# ServoCape_Rev2.net
KiCad netlist of a schematic drawn in EAGLE
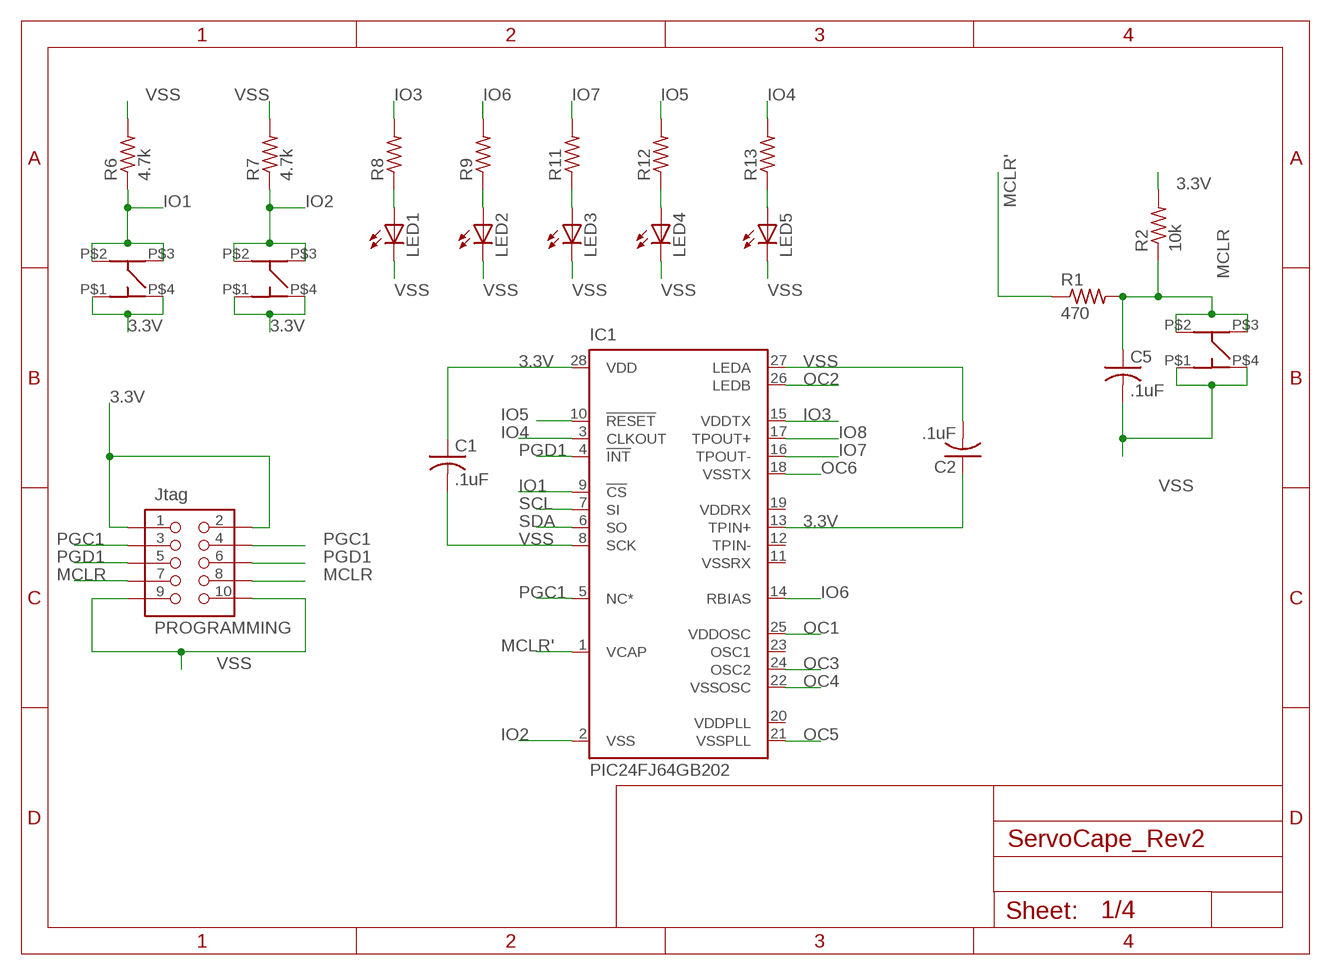
[diagram p0: schematic, sheet 1]
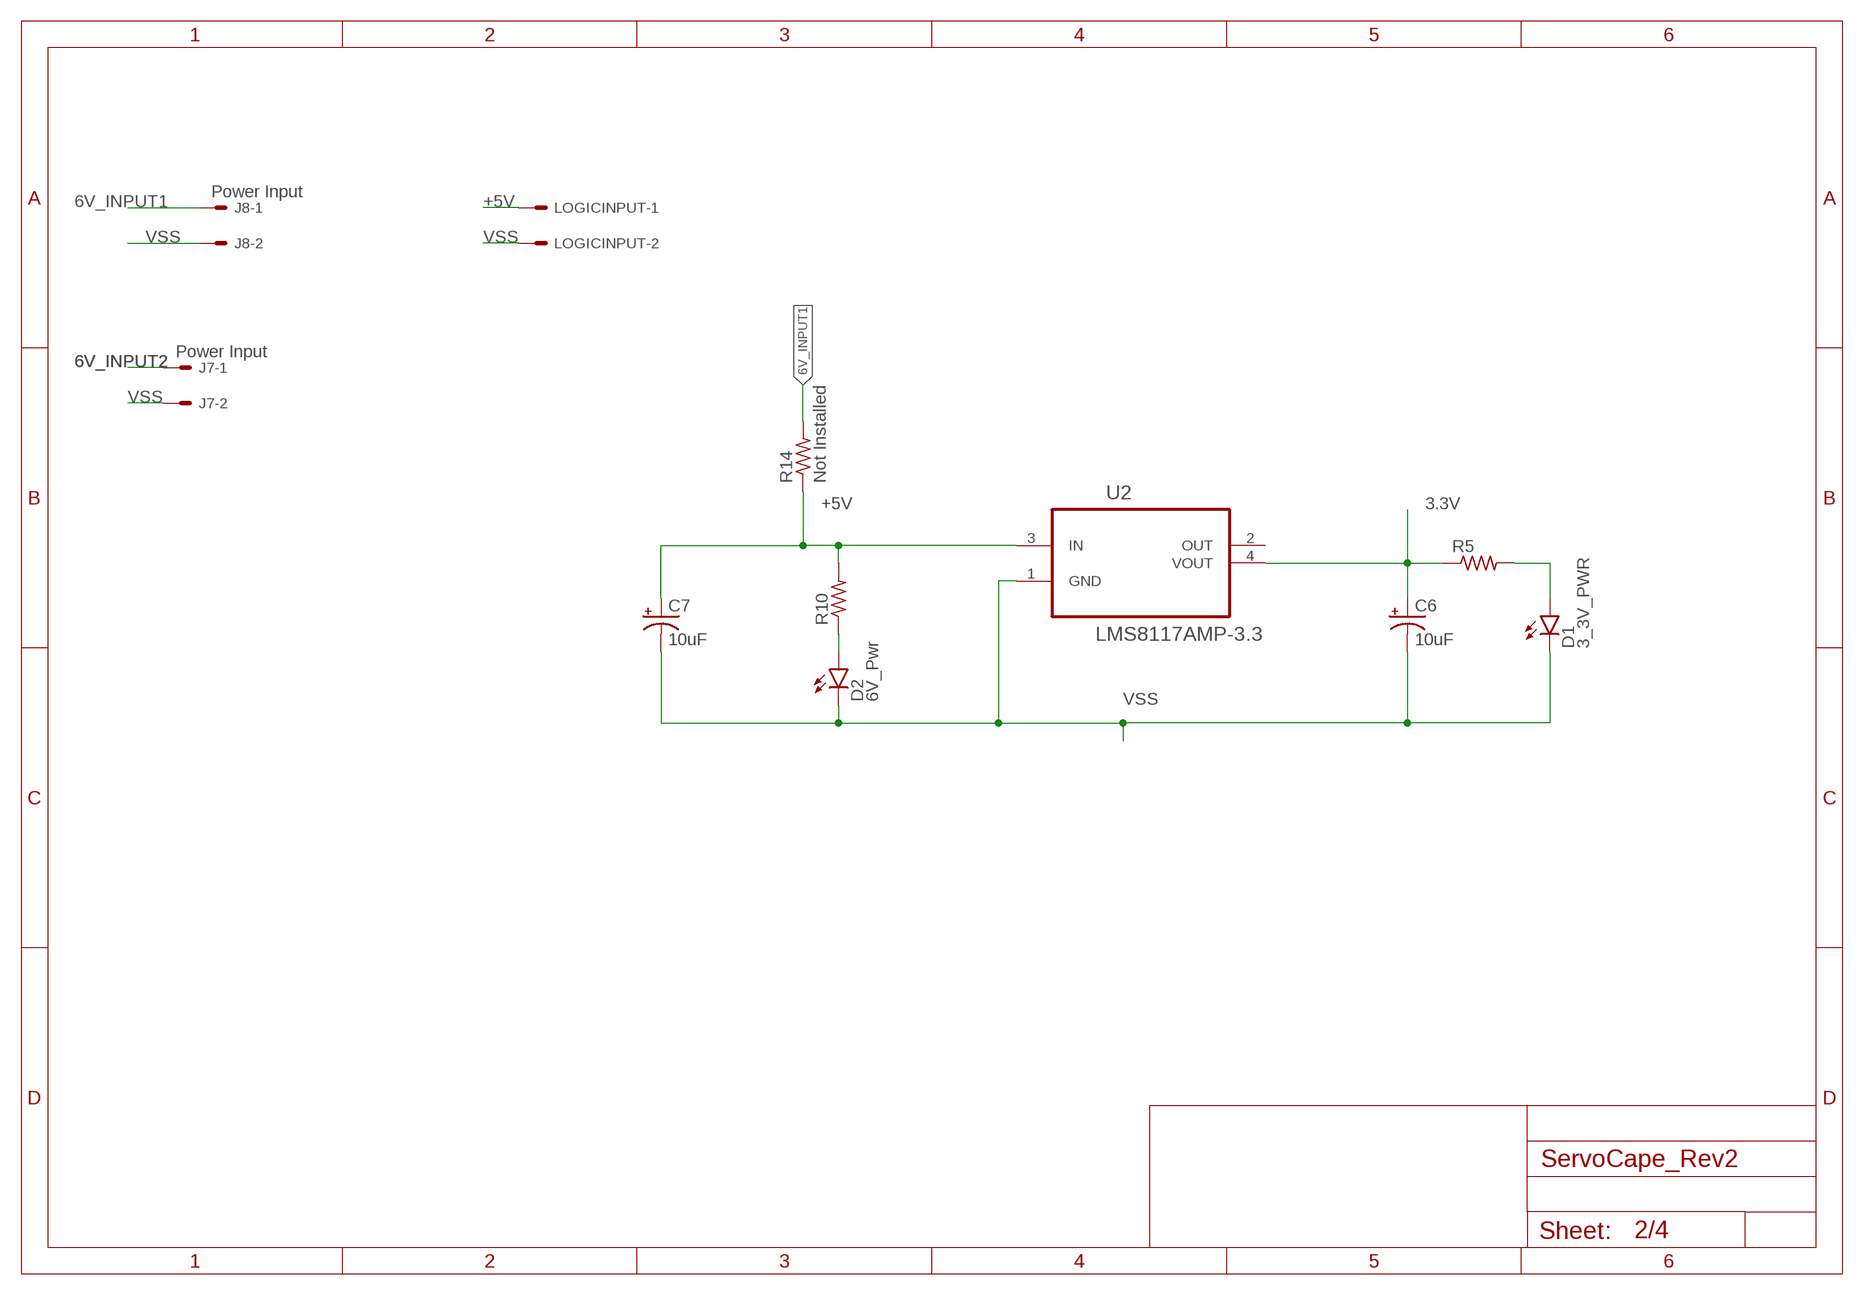
[diagram p1: schematic, sheet 2]
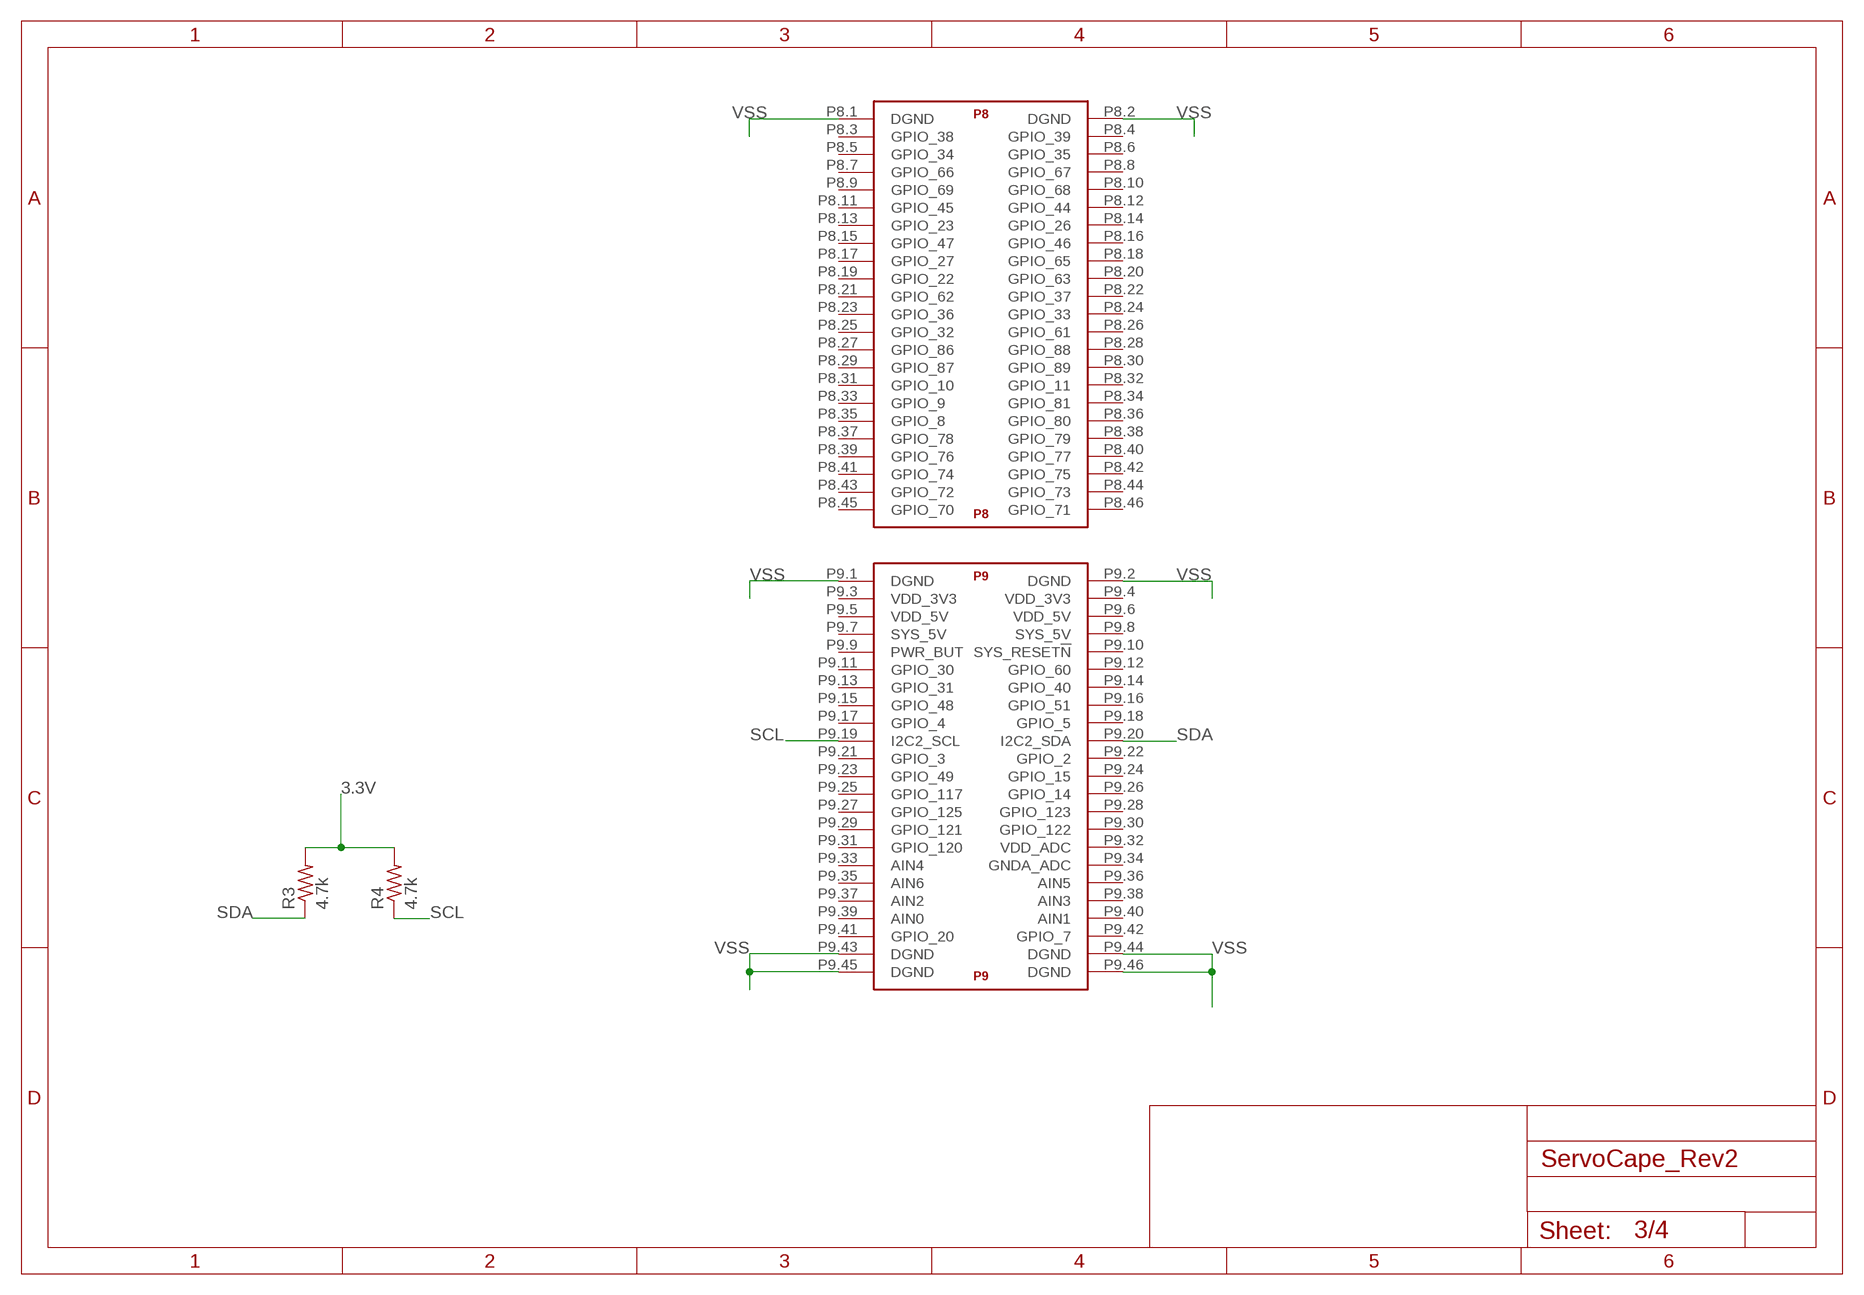
[diagram p2: schematic, sheet 3]
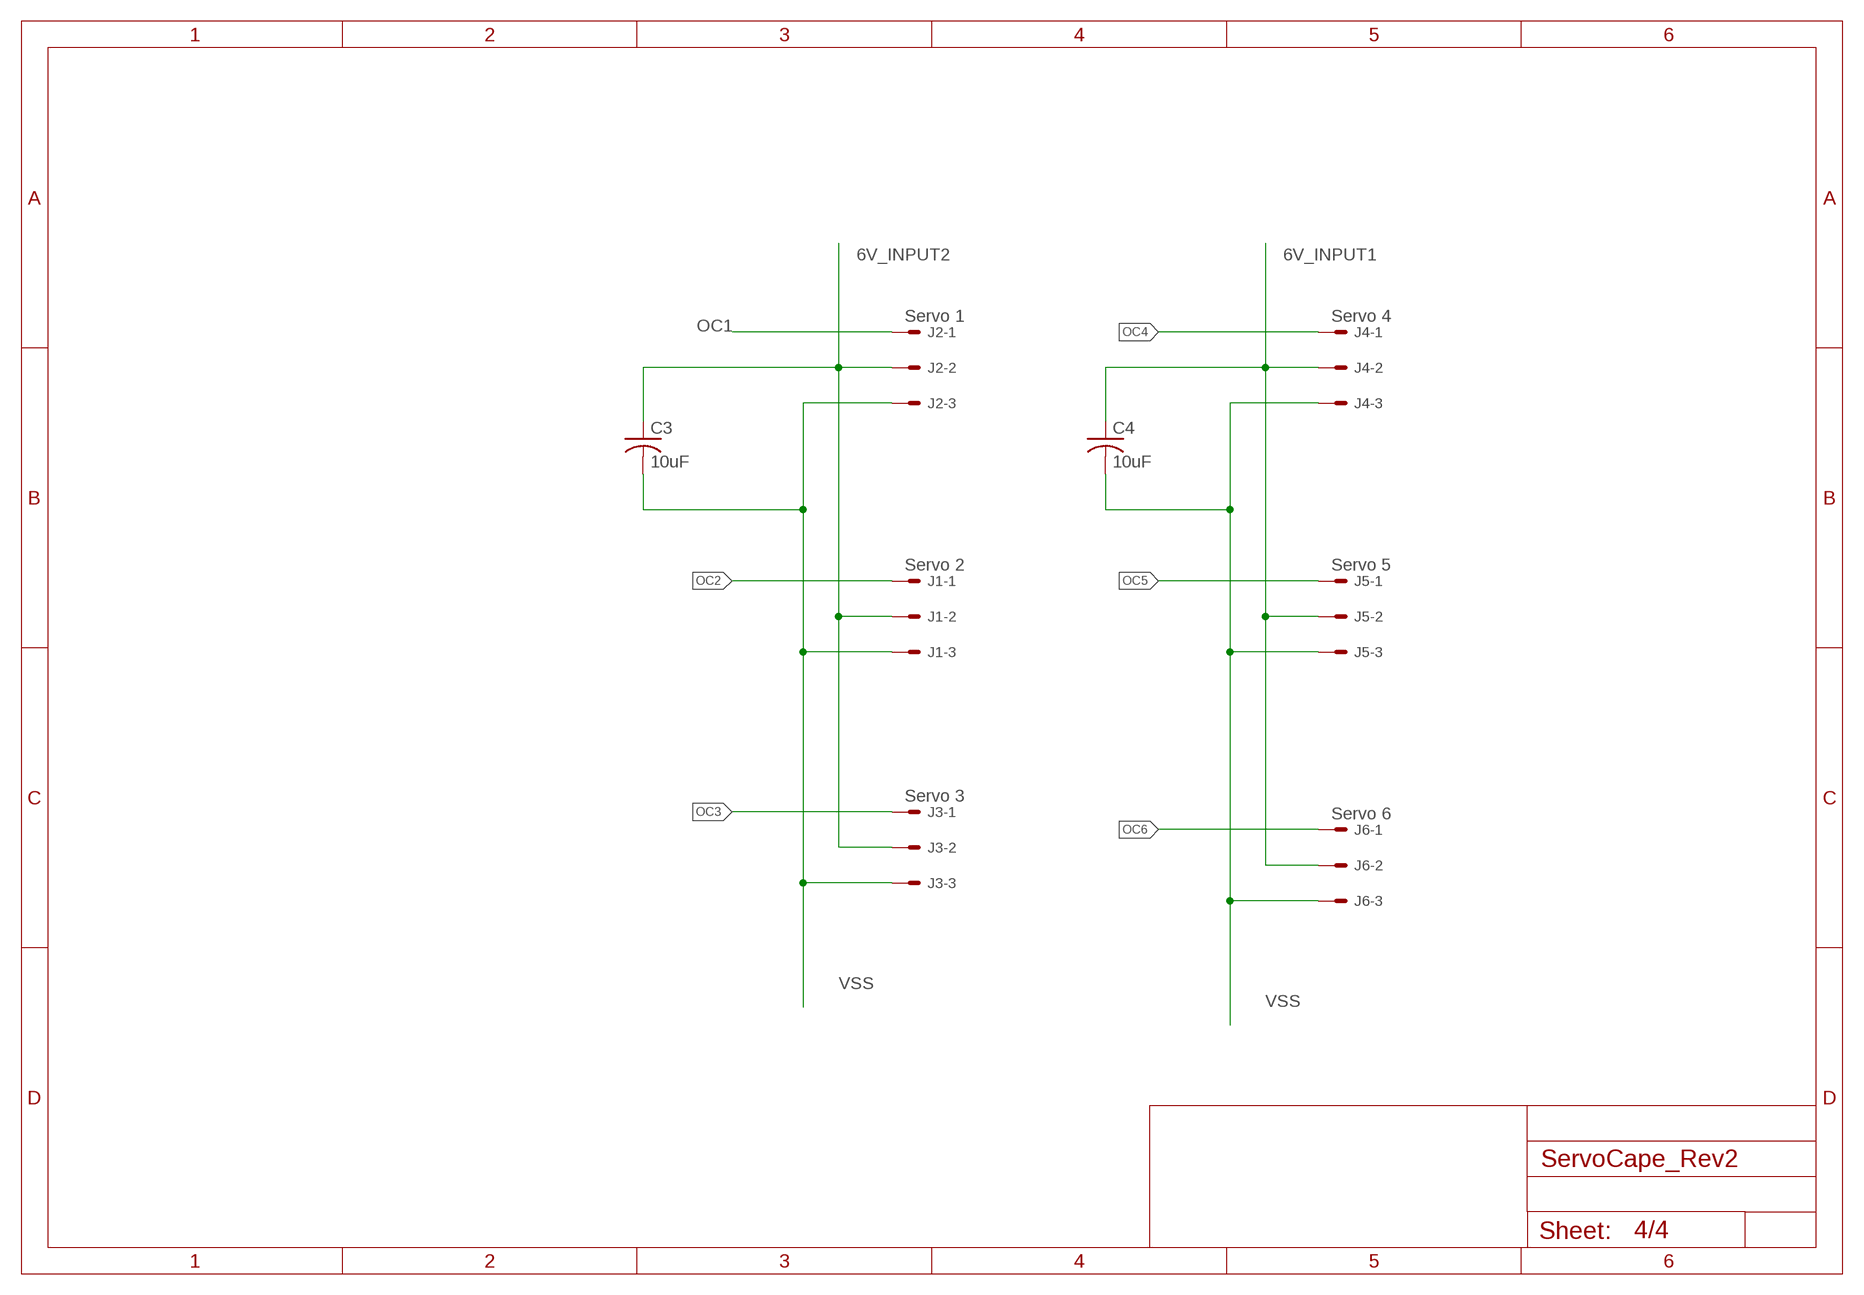
[diagram p3: schematic, sheet 4]

(export (version "E")
  (design (tool "Eeschema 10.0.6"))
  (components
    (comp (ref "C6")
      (value "10uF")
      (footprint "eagle-import:EIA3216")
      (libsource (lib "eagle-import") (part "10UF-16V-10%(TANT)"))
    )
    (comp (ref "C7")
      (value "10uF")
      (footprint "eagle-import:EIA3216")
      (libsource (lib "eagle-import") (part "10UF-16V-10%(TANT)"))
    )
    (comp (ref "D1")
      (value "3_3V_PWR")
      (footprint "eagle-import:FKIT-LED-1206")
      (libsource (lib "eagle-import") (part "LED-FKIT-1206"))
    )
    (comp (ref "D2")
      (value "6V_Pwr")
      (footprint "eagle-import:FKIT-LED-1206")
      (libsource (lib "eagle-import") (part "LED-FKIT-1206"))
    )
    (comp (ref "J7")
      (value "Power Input")
      (footprint "eagle-import:7395-02")
      (libsource (lib "eagle-import") (part "22-?-0205-7028"))
    )
    (comp (ref "J8")
      (value "Power Input")
      (footprint "eagle-import:7395-02")
      (libsource (lib "eagle-import") (part "22-?-0205-7028"))
    )
    (comp (ref "LOGICINPUT")
      (value "22-05-7028-02")
      (footprint "eagle-import:7395-02")
      (libsource (lib "eagle-import") (part "22-?-0205-7028"))
    )
    (comp (ref "R5")
      (value "R-US_R0805W")
      (footprint "eagle-import:R0805W")
      (libsource (lib "eagle-import") (part "R-US_R0805W"))
    )
    (comp (ref "R10")
      (value "R-US_R0805W")
      (footprint "eagle-import:R0805W")
      (libsource (lib "eagle-import") (part "R-US_R0805W"))
    )
    (comp (ref "R14")
      (value "Not Installed")
      (footprint "eagle-import:R0402")
      (libsource (lib "eagle-import") (part "R-US_R0402"))
    )
    (comp (ref "U2")
      (value "LMS8117AMP-3.3")
      (footprint "eagle-import:SOT230P696X180-4N")
      (libsource (lib "eagle-import") (part "LMS8117AMP-3.3"))
    )
    (comp (ref "C1")
      (value ".1uF")
      (footprint "eagle-import:C0805")
      (libsource (lib "eagle-import") (part "C-USC0805"))
    )
    (comp (ref "C2")
      (value ".1uF")
      (footprint "eagle-import:C0805")
      (libsource (lib "eagle-import") (part "C-USC0805"))
    )
    (comp (ref "C5")
      (value ".1uF")
      (footprint "eagle-import:C0805")
      (libsource (lib "eagle-import") (part "C-USC0805"))
    )
    (comp (ref "IC1")
      (value "PIC24FJ64GB202")
      (footprint "eagle-import:DIL28-3")
      (fields (field (name "MF") "MICROCHIP") (field (name "MPN") "ENC28J60/SP"))
      (libsource (lib "eagle-import") (part "ENC28J60SP"))
    )
    (comp (ref "LED1")
      (value "LED_LEDCHIPLED_1206")
      (footprint "eagle-import:LED_CHIPLED_1206")
      (libsource (lib "eagle-import") (part "LED_LEDCHIPLED_1206"))
    )
    (comp (ref "LED2")
      (value "LED_LEDCHIPLED_1206")
      (footprint "eagle-import:LED_CHIPLED_1206")
      (libsource (lib "eagle-import") (part "LED_LEDCHIPLED_1206"))
    )
    (comp (ref "LED3")
      (value "LED_LEDCHIPLED_1206")
      (footprint "eagle-import:LED_CHIPLED_1206")
      (libsource (lib "eagle-import") (part "LED_LEDCHIPLED_1206"))
    )
    (comp (ref "LED4")
      (value "LED_LEDCHIPLED_1206")
      (footprint "eagle-import:LED_CHIPLED_1206")
      (libsource (lib "eagle-import") (part "LED_LEDCHIPLED_1206"))
    )
    (comp (ref "LED5")
      (value "LED_LEDCHIPLED_1206")
      (footprint "eagle-import:LED_CHIPLED_1206")
      (libsource (lib "eagle-import") (part "LED_LEDCHIPLED_1206"))
    )
    (comp (ref "PROGRAMMING")
      (value "Jtag")
      (footprint "eagle-import:MOTHER-BOARD-REV5_10-PIN-SMD")
      (libsource (lib "eagle-import") (part "MOTHER-BOARD-REV5_PIN-CONNECTOR74089"))
    )
    (comp (ref "R1")
      (value "470")
      (footprint "eagle-import:R0805")
      (libsource (lib "eagle-import") (part "R-US_R0805"))
    )
    (comp (ref "R2")
      (value "10k")
      (footprint "eagle-import:R0805")
      (libsource (lib "eagle-import") (part "R-US_R0805"))
    )
    (comp (ref "R6")
      (value "4.7k")
      (footprint "eagle-import:R0805")
      (libsource (lib "eagle-import") (part "R-US_R0805"))
    )
    (comp (ref "R7")
      (value "4.7k")
      (footprint "eagle-import:R0805")
      (libsource (lib "eagle-import") (part "R-US_R0805"))
    )
    (comp (ref "R8")
      (value "R-US_M0805")
      (footprint "eagle-import:M0805")
      (libsource (lib "eagle-import") (part "R-US_M0805"))
    )
    (comp (ref "R9")
      (value "R-US_M0805")
      (footprint "eagle-import:M0805")
      (libsource (lib "eagle-import") (part "R-US_M0805"))
    )
    (comp (ref "R11")
      (value "R-US_M0805")
      (footprint "eagle-import:M0805")
      (libsource (lib "eagle-import") (part "R-US_M0805"))
    )
    (comp (ref "R12")
      (value "R-US_M0805")
      (footprint "eagle-import:M0805")
      (libsource (lib "eagle-import") (part "R-US_M0805"))
    )
    (comp (ref "R13")
      (value "R-US_M0805")
      (footprint "eagle-import:M0805")
      (libsource (lib "eagle-import") (part "R-US_M0805"))
    )
    (comp (ref "U$1")
      (value "Switch3")
      (footprint "eagle-import:MC32882_FINAL")
      (libsource (lib "eagle-import") (part "MC32882_SW"))
    )
    (comp (ref "U$4")
      (value "Switch1")
      (footprint "eagle-import:MC32882_FINAL")
      (libsource (lib "eagle-import") (part "MC32882_SW"))
    )
    (comp (ref "U$5")
      (value "Switch2")
      (footprint "eagle-import:MC32882_FINAL")
      (libsource (lib "eagle-import") (part "MC32882_SW"))
    )
    (comp (ref "R3")
      (value "4.7k")
      (footprint "eagle-import:R0805")
      (libsource (lib "eagle-import") (part "R-US_R0805"))
    )
    (comp (ref "R4")
      (value "4.7k")
      (footprint "eagle-import:R0805")
      (libsource (lib "eagle-import") (part "R-US_R0805"))
    )
    (comp (ref "U$2")
      (value "BEAGLE_BONE_BLACK_CAPE")
      (footprint "eagle-import:BEAGLE_BONE_BLACK_CAPE")
      (libsource (lib "eagle-import") (part "BEAGLE_BONE_BLACK_CAPE"))
    )
    (comp (ref "C3")
      (value "10uF")
      (footprint "eagle-import:C0805")
      (libsource (lib "eagle-import") (part "C-USC0805"))
    )
    (comp (ref "C4")
      (value "10uF")
      (footprint "eagle-import:C0805")
      (libsource (lib "eagle-import") (part "C-USC0805"))
    )
    (comp (ref "J1")
      (value "Servo 2")
      (footprint "eagle-import:7395-03")
      (libsource (lib "eagle-import") (part "22-?-0305-7038"))
    )
    (comp (ref "J2")
      (value "Servo 1")
      (footprint "eagle-import:7395-03")
      (libsource (lib "eagle-import") (part "22-?-0305-7038"))
    )
    (comp (ref "J3")
      (value "Servo 3")
      (footprint "eagle-import:7395-03")
      (libsource (lib "eagle-import") (part "22-?-0305-7038"))
    )
    (comp (ref "J4")
      (value "Servo 4")
      (footprint "eagle-import:7395-03")
      (libsource (lib "eagle-import") (part "22-?-0305-7038"))
    )
    (comp (ref "J5")
      (value "Servo 5")
      (footprint "eagle-import:7395-03")
      (libsource (lib "eagle-import") (part "22-?-0305-7038"))
    )
    (comp (ref "J6")
      (value "Servo 6")
      (footprint "eagle-import:7395-03")
      (libsource (lib "eagle-import") (part "22-?-0305-7038"))
    )
  )
  (nets
    (net (code "1") (name "+5V") (class "Default")
      (node (ref "C7") (pin "A") (pinfunction "+_A") (pintype "passive"))
      (node (ref "LOGICINPUT") (pin "1") (pinfunction "S_1") (pintype "passive"))
      (node (ref "R10") (pin "2") (pinfunction "2_2") (pintype "passive"))
      (node (ref "R14") (pin "1") (pinfunction "1_1") (pintype "passive"))
      (node (ref "U2") (pin "3") (pinfunction "IN_3") (pintype "power_in"))
    )
    (net (code "2") (name "3.3V") (class "Default")
      (node (ref "C1") (pin "1") (pinfunction "1_1") (pintype "passive"))
      (node (ref "C2") (pin "1") (pinfunction "1_1") (pintype "passive"))
      (node (ref "C6") (pin "A") (pinfunction "+_A") (pintype "passive"))
      (node (ref "IC1") (pin "13") (pinfunction "TPIN+_13") (pintype "input"))
      (node (ref "IC1") (pin "28") (pinfunction "VDD_28") (pintype "input"))
      (node (ref "PROGRAMMING") (pin "1") (pinfunction "P$1_1") (pintype "power_in"))
      (node (ref "PROGRAMMING") (pin "2") (pinfunction "P$2_2") (pintype "power_in"))
      (node (ref "R2") (pin "2") (pinfunction "2_2") (pintype "passive"))
      (node (ref "R3") (pin "2") (pinfunction "2_2") (pintype "passive"))
      (node (ref "R4") (pin "2") (pinfunction "2_2") (pintype "passive"))
      (node (ref "R5") (pin "1") (pinfunction "1_1") (pintype "passive"))
      (node (ref "U$4") (pin "P$1") (pinfunction "P1_P$1") (pintype "bidirectional"))
      (node (ref "U$4") (pin "P$4") (pinfunction "P4_P$4") (pintype "bidirectional"))
      (node (ref "U$5") (pin "P$1") (pinfunction "P1_P$1") (pintype "bidirectional"))
      (node (ref "U$5") (pin "P$4") (pinfunction "P4_P$4") (pintype "bidirectional"))
      (node (ref "U2") (pin "4") (pinfunction "VOUT_4") (pintype "power_in"))
    )
    (net (code "3") (name "6V_INPUT1") (class "Default")
      (node (ref "C4") (pin "1") (pinfunction "1_1") (pintype "passive"))
      (node (ref "J4") (pin "2") (pinfunction "S_2") (pintype "passive"))
      (node (ref "J5") (pin "2") (pinfunction "S_2") (pintype "passive"))
      (node (ref "J6") (pin "2") (pinfunction "S_2") (pintype "passive"))
      (node (ref "J8") (pin "1") (pinfunction "S_1") (pintype "passive"))
      (node (ref "R14") (pin "2") (pinfunction "2_2") (pintype "passive"))
    )
    (net (code "4") (name "6V_INPUT2") (class "Default")
      (node (ref "C3") (pin "1") (pinfunction "1_1") (pintype "passive"))
      (node (ref "J1") (pin "2") (pinfunction "S_2") (pintype "passive"))
      (node (ref "J2") (pin "2") (pinfunction "S_2") (pintype "passive"))
      (node (ref "J3") (pin "2") (pinfunction "S_2") (pintype "passive"))
      (node (ref "J7") (pin "1") (pinfunction "S_1") (pintype "passive"))
    )
    (net (code "5") (name "IO1") (class "Default")
      (node (ref "IC1") (pin "9") (pinfunction "~{CS}_9") (pintype "input"))
      (node (ref "R6") (pin "1") (pinfunction "1_1") (pintype "passive"))
      (node (ref "U$4") (pin "P$2") (pinfunction "P2_P$2") (pintype "bidirectional"))
      (node (ref "U$4") (pin "P$3") (pinfunction "P3_P$3") (pintype "bidirectional"))
    )
    (net (code "6") (name "IO2") (class "Default")
      (node (ref "IC1") (pin "2") (pinfunction "VSS_2") (pintype "input"))
      (node (ref "R7") (pin "1") (pinfunction "1_1") (pintype "passive"))
      (node (ref "U$5") (pin "P$2") (pinfunction "P2_P$2") (pintype "bidirectional"))
      (node (ref "U$5") (pin "P$3") (pinfunction "P3_P$3") (pintype "bidirectional"))
    )
    (net (code "7") (name "IO3") (class "Default")
      (node (ref "IC1") (pin "15") (pinfunction "VDDTX_15") (pintype "input"))
      (node (ref "R8") (pin "2") (pinfunction "2_2") (pintype "passive"))
    )
    (net (code "8") (name "IO4") (class "Default")
      (node (ref "IC1") (pin "3") (pinfunction "CLKOUT_3") (pintype "output"))
      (node (ref "R13") (pin "2") (pinfunction "2_2") (pintype "passive"))
    )
    (net (code "9") (name "IO5") (class "Default")
      (node (ref "IC1") (pin "10") (pinfunction "~{RESET}_10") (pintype "input"))
      (node (ref "R12") (pin "2") (pinfunction "2_2") (pintype "passive"))
    )
    (net (code "10") (name "IO6") (class "Default")
      (node (ref "IC1") (pin "14") (pinfunction "RBIAS_14") (pintype "input"))
      (node (ref "R9") (pin "2") (pinfunction "2_2") (pintype "passive"))
    )
    (net (code "11") (name "IO7") (class "Default")
      (node (ref "IC1") (pin "16") (pinfunction "TPOUT-_16") (pintype "output"))
      (node (ref "R11") (pin "2") (pinfunction "2_2") (pintype "passive"))
    )
    (net (code "12") (name "IO8") (class "Default")
      (node (ref "IC1") (pin "17") (pinfunction "TPOUT+_17") (pintype "output"))
    )
    (net (code "13") (name "MCLR") (class "Default")
      (node (ref "C5") (pin "1") (pinfunction "1_1") (pintype "passive"))
      (node (ref "PROGRAMMING") (pin "7") (pinfunction "P$7_7") (pintype "power_in"))
      (node (ref "PROGRAMMING") (pin "8") (pinfunction "P$8_8") (pintype "power_in"))
      (node (ref "R1") (pin "2") (pinfunction "2_2") (pintype "passive"))
      (node (ref "R2") (pin "1") (pinfunction "1_1") (pintype "passive"))
      (node (ref "U$1") (pin "P$2") (pinfunction "P2_P$2") (pintype "bidirectional"))
      (node (ref "U$1") (pin "P$3") (pinfunction "P3_P$3") (pintype "bidirectional"))
    )
    (net (code "14") (name "MCLR'") (class "Default")
      (node (ref "IC1") (pin "1") (pinfunction "VCAP_1") (pintype "input"))
      (node (ref "R1") (pin "1") (pinfunction "1_1") (pintype "passive"))
    )
    (net (code "15") (name "Net-(D1-PadA)") (class "Default")
      (node (ref "D1") (pin "A") (pinfunction "A_A") (pintype "passive"))
      (node (ref "R5") (pin "2") (pinfunction "2_2") (pintype "passive"))
    )
    (net (code "16") (name "Net-(D2-PadA)") (class "Default")
      (node (ref "D2") (pin "A") (pinfunction "A_A") (pintype "passive"))
      (node (ref "R10") (pin "1") (pinfunction "1_1") (pintype "passive"))
    )
    (net (code "17") (name "Net-(LED1-PadA)") (class "Default")
      (node (ref "LED1") (pin "A") (pinfunction "A_A") (pintype "passive"))
      (node (ref "R8") (pin "1") (pinfunction "1_1") (pintype "passive"))
    )
    (net (code "18") (name "Net-(LED2-PadA)") (class "Default")
      (node (ref "LED2") (pin "A") (pinfunction "A_A") (pintype "passive"))
      (node (ref "R9") (pin "1") (pinfunction "1_1") (pintype "passive"))
    )
    (net (code "19") (name "Net-(LED3-PadA)") (class "Default")
      (node (ref "LED3") (pin "A") (pinfunction "A_A") (pintype "passive"))
      (node (ref "R11") (pin "1") (pinfunction "1_1") (pintype "passive"))
    )
    (net (code "20") (name "Net-(LED4-PadA)") (class "Default")
      (node (ref "LED4") (pin "A") (pinfunction "A_A") (pintype "passive"))
      (node (ref "R12") (pin "1") (pinfunction "1_1") (pintype "passive"))
    )
    (net (code "21") (name "Net-(LED5-PadA)") (class "Default")
      (node (ref "LED5") (pin "A") (pinfunction "A_A") (pintype "passive"))
      (node (ref "R13") (pin "1") (pinfunction "1_1") (pintype "passive"))
    )
    (net (code "22") (name "OC1") (class "Default")
      (node (ref "IC1") (pin "25") (pinfunction "VDDOSC_25") (pintype "input"))
      (node (ref "J2") (pin "1") (pinfunction "S_1") (pintype "passive"))
    )
    (net (code "23") (name "OC2") (class "Default")
      (node (ref "IC1") (pin "26") (pinfunction "LEDB_26") (pintype "output"))
      (node (ref "J1") (pin "1") (pinfunction "S_1") (pintype "passive"))
    )
    (net (code "24") (name "OC3") (class "Default")
      (node (ref "IC1") (pin "24") (pinfunction "OSC2_24") (pintype "output"))
      (node (ref "J3") (pin "1") (pinfunction "S_1") (pintype "passive"))
    )
    (net (code "25") (name "OC4") (class "Default")
      (node (ref "IC1") (pin "22") (pinfunction "VSSOSC_22") (pintype "input"))
      (node (ref "J4") (pin "1") (pinfunction "S_1") (pintype "passive"))
    )
    (net (code "26") (name "OC5") (class "Default")
      (node (ref "IC1") (pin "21") (pinfunction "VSSPLL_21") (pintype "input"))
      (node (ref "J5") (pin "1") (pinfunction "S_1") (pintype "passive"))
    )
    (net (code "27") (name "OC6") (class "Default")
      (node (ref "IC1") (pin "18") (pinfunction "VSSTX_18") (pintype "input"))
      (node (ref "J6") (pin "1") (pinfunction "S_1") (pintype "passive"))
    )
    (net (code "28") (name "PGC1") (class "Default")
      (node (ref "IC1") (pin "5") (pinfunction "NC*_5") (pintype "output"))
      (node (ref "PROGRAMMING") (pin "3") (pinfunction "P$3_3") (pintype "power_in"))
      (node (ref "PROGRAMMING") (pin "4") (pinfunction "P$4_4") (pintype "power_in"))
    )
    (net (code "29") (name "PGD1") (class "Default")
      (node (ref "IC1") (pin "4") (pinfunction "~{INT}_4") (pintype "output"))
      (node (ref "PROGRAMMING") (pin "5") (pinfunction "P$5_5") (pintype "power_in"))
      (node (ref "PROGRAMMING") (pin "6") (pinfunction "P$6_6") (pintype "power_in"))
    )
    (net (code "30") (name "SCL") (class "Default")
      (node (ref "IC1") (pin "7") (pinfunction "SI_7") (pintype "input"))
      (node (ref "R4") (pin "1") (pinfunction "1_1") (pintype "passive"))
      (node (ref "U$2") (pin "P9.19") (pinfunction "I2C2_SCL_P9.19") (pintype "bidirectional"))
    )
    (net (code "31") (name "SDA") (class "Default")
      (node (ref "IC1") (pin "6") (pinfunction "SO_6") (pintype "output"))
      (node (ref "R3") (pin "1") (pinfunction "1_1") (pintype "passive"))
      (node (ref "U$2") (pin "P9.20") (pinfunction "I2C2_SDA_P9.20") (pintype "bidirectional"))
    )
    (net (code "32") (name "VSS") (class "Default")
      (node (ref "C1") (pin "2") (pinfunction "2_2") (pintype "passive"))
      (node (ref "C2") (pin "2") (pinfunction "2_2") (pintype "passive"))
      (node (ref "C3") (pin "2") (pinfunction "2_2") (pintype "passive"))
      (node (ref "C4") (pin "2") (pinfunction "2_2") (pintype "passive"))
      (node (ref "C5") (pin "2") (pinfunction "2_2") (pintype "passive"))
      (node (ref "C6") (pin "C") (pinfunction "-_C") (pintype "passive"))
      (node (ref "C7") (pin "C") (pinfunction "-_C") (pintype "passive"))
      (node (ref "D1") (pin "C") (pinfunction "C_C") (pintype "passive"))
      (node (ref "D2") (pin "C") (pinfunction "C_C") (pintype "passive"))
      (node (ref "IC1") (pin "27") (pinfunction "LEDA_27") (pintype "output"))
      (node (ref "IC1") (pin "8") (pinfunction "SCK_8") (pintype "input"))
      (node (ref "J1") (pin "3") (pinfunction "S_3") (pintype "passive"))
      (node (ref "J2") (pin "3") (pinfunction "S_3") (pintype "passive"))
      (node (ref "J3") (pin "3") (pinfunction "S_3") (pintype "passive"))
      (node (ref "J4") (pin "3") (pinfunction "S_3") (pintype "passive"))
      (node (ref "J5") (pin "3") (pinfunction "S_3") (pintype "passive"))
      (node (ref "J6") (pin "3") (pinfunction "S_3") (pintype "passive"))
      (node (ref "J7") (pin "2") (pinfunction "S_2") (pintype "passive"))
      (node (ref "J8") (pin "2") (pinfunction "S_2") (pintype "passive"))
      (node (ref "LED1") (pin "C") (pinfunction "C_C") (pintype "passive"))
      (node (ref "LED2") (pin "C") (pinfunction "C_C") (pintype "passive"))
      (node (ref "LED3") (pin "C") (pinfunction "C_C") (pintype "passive"))
      (node (ref "LED4") (pin "C") (pinfunction "C_C") (pintype "passive"))
      (node (ref "LED5") (pin "C") (pinfunction "C_C") (pintype "passive"))
      (node (ref "LOGICINPUT") (pin "2") (pinfunction "S_2") (pintype "passive"))
      (node (ref "PROGRAMMING") (pin "10") (pinfunction "P$10_10") (pintype "power_in"))
      (node (ref "PROGRAMMING") (pin "9") (pinfunction "P$9_9") (pintype "power_in"))
      (node (ref "R6") (pin "2") (pinfunction "2_2") (pintype "passive"))
      (node (ref "R7") (pin "2") (pinfunction "2_2") (pintype "passive"))
      (node (ref "U$1") (pin "P$1") (pinfunction "P1_P$1") (pintype "bidirectional"))
      (node (ref "U$1") (pin "P$4") (pinfunction "P4_P$4") (pintype "bidirectional"))
      (node (ref "U$2") (pin "P8.1") (pinfunction "DGND_P8.1") (pintype "bidirectional"))
      (node (ref "U$2") (pin "P8.2") (pinfunction "DGND_P8.2") (pintype "bidirectional"))
      (node (ref "U$2") (pin "P9.1") (pinfunction "DGND_P9.1") (pintype "bidirectional"))
      (node (ref "U$2") (pin "P9.2") (pinfunction "DGND_P9.2") (pintype "bidirectional"))
      (node (ref "U$2") (pin "P9.43") (pinfunction "DGND_P9.43") (pintype "bidirectional"))
      (node (ref "U$2") (pin "P9.44") (pinfunction "DGND_P9.44") (pintype "bidirectional"))
      (node (ref "U$2") (pin "P9.45") (pinfunction "DGND_P9.45") (pintype "bidirectional"))
      (node (ref "U$2") (pin "P9.46") (pinfunction "DGND_P9.46") (pintype "bidirectional"))
      (node (ref "U2") (pin "1") (pinfunction "GND_1") (pintype "passive"))
    )
    (net (code "33") (name "unconnected-(IC1-OSC1-Pad23)") (class "Default")
      (node (ref "IC1") (pin "23") (pinfunction "OSC1_23") (pintype "input"))
    )
    (net (code "34") (name "unconnected-(IC1-TPIN--Pad12)") (class "Default")
      (node (ref "IC1") (pin "12") (pinfunction "TPIN-_12") (pintype "input"))
    )
    (net (code "35") (name "unconnected-(IC1-VDDPLL-Pad20)") (class "Default")
      (node (ref "IC1") (pin "20") (pinfunction "VDDPLL_20") (pintype "input"))
    )
    (net (code "36") (name "unconnected-(IC1-VDDRX-Pad19)") (class "Default")
      (node (ref "IC1") (pin "19") (pinfunction "VDDRX_19") (pintype "input"))
    )
    (net (code "37") (name "unconnected-(IC1-VSSRX-Pad11)") (class "Default")
      (node (ref "IC1") (pin "11") (pinfunction "VSSRX_11") (pintype "input"))
    )
    (net (code "38") (name "unconnected-(U$2A-GPIO_8-PadP8.35)") (class "Default")
      (node (ref "U$2") (pin "P8.35") (pinfunction "GPIO_8_P8.35") (pintype "bidirectional"))
    )
    (net (code "39") (name "unconnected-(U$2A-GPIO_9-PadP8.33)") (class "Default")
      (node (ref "U$2") (pin "P8.33") (pinfunction "GPIO_9_P8.33") (pintype "bidirectional"))
    )
    (net (code "40") (name "unconnected-(U$2A-GPIO_10-PadP8.31)") (class "Default")
      (node (ref "U$2") (pin "P8.31") (pinfunction "GPIO_10_P8.31") (pintype "bidirectional"))
    )
    (net (code "41") (name "unconnected-(U$2A-GPIO_11-PadP8.32)") (class "Default")
      (node (ref "U$2") (pin "P8.32") (pinfunction "GPIO_11_P8.32") (pintype "bidirectional"))
    )
    (net (code "42") (name "unconnected-(U$2A-GPIO_22-PadP8.19)") (class "Default")
      (node (ref "U$2") (pin "P8.19") (pinfunction "GPIO_22_P8.19") (pintype "bidirectional"))
    )
    (net (code "43") (name "unconnected-(U$2A-GPIO_23-PadP8.13)") (class "Default")
      (node (ref "U$2") (pin "P8.13") (pinfunction "GPIO_23_P8.13") (pintype "bidirectional"))
    )
    (net (code "44") (name "unconnected-(U$2A-GPIO_26-PadP8.14)") (class "Default")
      (node (ref "U$2") (pin "P8.14") (pinfunction "GPIO_26_P8.14") (pintype "bidirectional"))
    )
    (net (code "45") (name "unconnected-(U$2A-GPIO_27-PadP8.17)") (class "Default")
      (node (ref "U$2") (pin "P8.17") (pinfunction "GPIO_27_P8.17") (pintype "bidirectional"))
    )
    (net (code "46") (name "unconnected-(U$2A-GPIO_32-PadP8.25)") (class "Default")
      (node (ref "U$2") (pin "P8.25") (pinfunction "GPIO_32_P8.25") (pintype "bidirectional"))
    )
    (net (code "47") (name "unconnected-(U$2A-GPIO_33-PadP8.24)") (class "Default")
      (node (ref "U$2") (pin "P8.24") (pinfunction "GPIO_33_P8.24") (pintype "bidirectional"))
    )
    (net (code "48") (name "unconnected-(U$2A-GPIO_34-PadP8.5)") (class "Default")
      (node (ref "U$2") (pin "P8.5") (pinfunction "GPIO_34_P8.5") (pintype "bidirectional"))
    )
    (net (code "49") (name "unconnected-(U$2A-GPIO_35-PadP8.6)") (class "Default")
      (node (ref "U$2") (pin "P8.6") (pinfunction "GPIO_35_P8.6") (pintype "bidirectional"))
    )
    (net (code "50") (name "unconnected-(U$2A-GPIO_36-PadP8.23)") (class "Default")
      (node (ref "U$2") (pin "P8.23") (pinfunction "GPIO_36_P8.23") (pintype "bidirectional"))
    )
    (net (code "51") (name "unconnected-(U$2A-GPIO_37-PadP8.22)") (class "Default")
      (node (ref "U$2") (pin "P8.22") (pinfunction "GPIO_37_P8.22") (pintype "bidirectional"))
    )
    (net (code "52") (name "unconnected-(U$2A-GPIO_38-PadP8.3)") (class "Default")
      (node (ref "U$2") (pin "P8.3") (pinfunction "GPIO_38_P8.3") (pintype "bidirectional"))
    )
    (net (code "53") (name "unconnected-(U$2A-GPIO_39-PadP8.4)") (class "Default")
      (node (ref "U$2") (pin "P8.4") (pinfunction "GPIO_39_P8.4") (pintype "bidirectional"))
    )
    (net (code "54") (name "unconnected-(U$2A-GPIO_44-PadP8.12)") (class "Default")
      (node (ref "U$2") (pin "P8.12") (pinfunction "GPIO_44_P8.12") (pintype "bidirectional"))
    )
    (net (code "55") (name "unconnected-(U$2A-GPIO_45-PadP8.11)") (class "Default")
      (node (ref "U$2") (pin "P8.11") (pinfunction "GPIO_45_P8.11") (pintype "bidirectional"))
    )
    (net (code "56") (name "unconnected-(U$2A-GPIO_46-PadP8.16)") (class "Default")
      (node (ref "U$2") (pin "P8.16") (pinfunction "GPIO_46_P8.16") (pintype "bidirectional"))
    )
    (net (code "57") (name "unconnected-(U$2A-GPIO_47-PadP8.15)") (class "Default")
      (node (ref "U$2") (pin "P8.15") (pinfunction "GPIO_47_P8.15") (pintype "bidirectional"))
    )
    (net (code "58") (name "unconnected-(U$2A-GPIO_61-PadP8.26)") (class "Default")
      (node (ref "U$2") (pin "P8.26") (pinfunction "GPIO_61_P8.26") (pintype "bidirectional"))
    )
    (net (code "59") (name "unconnected-(U$2A-GPIO_62-PadP8.21)") (class "Default")
      (node (ref "U$2") (pin "P8.21") (pinfunction "GPIO_62_P8.21") (pintype "bidirectional"))
    )
    (net (code "60") (name "unconnected-(U$2A-GPIO_63-PadP8.20)") (class "Default")
      (node (ref "U$2") (pin "P8.20") (pinfunction "GPIO_63_P8.20") (pintype "bidirectional"))
    )
    (net (code "61") (name "unconnected-(U$2A-GPIO_65-PadP8.18)") (class "Default")
      (node (ref "U$2") (pin "P8.18") (pinfunction "GPIO_65_P8.18") (pintype "bidirectional"))
    )
    (net (code "62") (name "unconnected-(U$2A-GPIO_66-PadP8.7)") (class "Default")
      (node (ref "U$2") (pin "P8.7") (pinfunction "GPIO_66_P8.7") (pintype "bidirectional"))
    )
    (net (code "63") (name "unconnected-(U$2A-GPIO_67-PadP8.8)") (class "Default")
      (node (ref "U$2") (pin "P8.8") (pinfunction "GPIO_67_P8.8") (pintype "bidirectional"))
    )
    (net (code "64") (name "unconnected-(U$2A-GPIO_68-PadP8.10)") (class "Default")
      (node (ref "U$2") (pin "P8.10") (pinfunction "GPIO_68_P8.10") (pintype "bidirectional"))
    )
    (net (code "65") (name "unconnected-(U$2A-GPIO_69-PadP8.9)") (class "Default")
      (node (ref "U$2") (pin "P8.9") (pinfunction "GPIO_69_P8.9") (pintype "bidirectional"))
    )
    (net (code "66") (name "unconnected-(U$2A-GPIO_70-PadP8.45)") (class "Default")
      (node (ref "U$2") (pin "P8.45") (pinfunction "GPIO_70_P8.45") (pintype "bidirectional"))
    )
    (net (code "67") (name "unconnected-(U$2A-GPIO_71-PadP8.46)") (class "Default")
      (node (ref "U$2") (pin "P8.46") (pinfunction "GPIO_71_P8.46") (pintype "bidirectional"))
    )
    (net (code "68") (name "unconnected-(U$2A-GPIO_72-PadP8.43)") (class "Default")
      (node (ref "U$2") (pin "P8.43") (pinfunction "GPIO_72_P8.43") (pintype "bidirectional"))
    )
    (net (code "69") (name "unconnected-(U$2A-GPIO_73-PadP8.44)") (class "Default")
      (node (ref "U$2") (pin "P8.44") (pinfunction "GPIO_73_P8.44") (pintype "bidirectional"))
    )
    (net (code "70") (name "unconnected-(U$2A-GPIO_74-PadP8.41)") (class "Default")
      (node (ref "U$2") (pin "P8.41") (pinfunction "GPIO_74_P8.41") (pintype "bidirectional"))
    )
    (net (code "71") (name "unconnected-(U$2A-GPIO_75-PadP8.42)") (class "Default")
      (node (ref "U$2") (pin "P8.42") (pinfunction "GPIO_75_P8.42") (pintype "bidirectional"))
    )
    (net (code "72") (name "unconnected-(U$2A-GPIO_76-PadP8.39)") (class "Default")
      (node (ref "U$2") (pin "P8.39") (pinfunction "GPIO_76_P8.39") (pintype "bidirectional"))
    )
    (net (code "73") (name "unconnected-(U$2A-GPIO_77-PadP8.40)") (class "Default")
      (node (ref "U$2") (pin "P8.40") (pinfunction "GPIO_77_P8.40") (pintype "bidirectional"))
    )
    (net (code "74") (name "unconnected-(U$2A-GPIO_78-PadP8.37)") (class "Default")
      (node (ref "U$2") (pin "P8.37") (pinfunction "GPIO_78_P8.37") (pintype "bidirectional"))
    )
    (net (code "75") (name "unconnected-(U$2A-GPIO_79-PadP8.38)") (class "Default")
      (node (ref "U$2") (pin "P8.38") (pinfunction "GPIO_79_P8.38") (pintype "bidirectional"))
    )
    (net (code "76") (name "unconnected-(U$2A-GPIO_80-PadP8.36)") (class "Default")
      (node (ref "U$2") (pin "P8.36") (pinfunction "GPIO_80_P8.36") (pintype "bidirectional"))
    )
    (net (code "77") (name "unconnected-(U$2A-GPIO_81-PadP8.34)") (class "Default")
      (node (ref "U$2") (pin "P8.34") (pinfunction "GPIO_81_P8.34") (pintype "bidirectional"))
    )
    (net (code "78") (name "unconnected-(U$2A-GPIO_86-PadP8.27)") (class "Default")
      (node (ref "U$2") (pin "P8.27") (pinfunction "GPIO_86_P8.27") (pintype "bidirectional"))
    )
    (net (code "79") (name "unconnected-(U$2A-GPIO_87-PadP8.29)") (class "Default")
      (node (ref "U$2") (pin "P8.29") (pinfunction "GPIO_87_P8.29") (pintype "bidirectional"))
    )
    (net (code "80") (name "unconnected-(U$2A-GPIO_88-PadP8.28)") (class "Default")
      (node (ref "U$2") (pin "P8.28") (pinfunction "GPIO_88_P8.28") (pintype "bidirectional"))
    )
    (net (code "81") (name "unconnected-(U$2A-GPIO_89-PadP8.30)") (class "Default")
      (node (ref "U$2") (pin "P8.30") (pinfunction "GPIO_89_P8.30") (pintype "bidirectional"))
    )
    (net (code "82") (name "unconnected-(U$2B-AIN0-PadP9.39)") (class "Default")
      (node (ref "U$2") (pin "P9.39") (pinfunction "AIN0_P9.39") (pintype "bidirectional"))
    )
    (net (code "83") (name "unconnected-(U$2B-AIN1-PadP9.40)") (class "Default")
      (node (ref "U$2") (pin "P9.40") (pinfunction "AIN1_P9.40") (pintype "bidirectional"))
    )
    (net (code "84") (name "unconnected-(U$2B-AIN2-PadP9.37)") (class "Default")
      (node (ref "U$2") (pin "P9.37") (pinfunction "AIN2_P9.37") (pintype "bidirectional"))
    )
    (net (code "85") (name "unconnected-(U$2B-AIN3-PadP9.38)") (class "Default")
      (node (ref "U$2") (pin "P9.38") (pinfunction "AIN3_P9.38") (pintype "bidirectional"))
    )
    (net (code "86") (name "unconnected-(U$2B-AIN4-PadP9.33)") (class "Default")
      (node (ref "U$2") (pin "P9.33") (pinfunction "AIN4_P9.33") (pintype "bidirectional"))
    )
    (net (code "87") (name "unconnected-(U$2B-AIN5-PadP9.36)") (class "Default")
      (node (ref "U$2") (pin "P9.36") (pinfunction "AIN5_P9.36") (pintype "bidirectional"))
    )
    (net (code "88") (name "unconnected-(U$2B-AIN6-PadP9.35)") (class "Default")
      (node (ref "U$2") (pin "P9.35") (pinfunction "AIN6_P9.35") (pintype "bidirectional"))
    )
    (net (code "89") (name "unconnected-(U$2B-GNDA_ADC-PadP9.34)") (class "Default")
      (node (ref "U$2") (pin "P9.34") (pinfunction "GNDA_ADC_P9.34") (pintype "bidirectional"))
    )
    (net (code "90") (name "unconnected-(U$2B-GPIO_2-PadP9.22)") (class "Default")
      (node (ref "U$2") (pin "P9.22") (pinfunction "GPIO_2_P9.22") (pintype "bidirectional"))
    )
    (net (code "91") (name "unconnected-(U$2B-GPIO_3-PadP9.21)") (class "Default")
      (node (ref "U$2") (pin "P9.21") (pinfunction "GPIO_3_P9.21") (pintype "bidirectional"))
    )
    (net (code "92") (name "unconnected-(U$2B-GPIO_4-PadP9.17)") (class "Default")
      (node (ref "U$2") (pin "P9.17") (pinfunction "GPIO_4_P9.17") (pintype "bidirectional"))
    )
    (net (code "93") (name "unconnected-(U$2B-GPIO_5-PadP9.18)") (class "Default")
      (node (ref "U$2") (pin "P9.18") (pinfunction "GPIO_5_P9.18") (pintype "bidirectional"))
    )
    (net (code "94") (name "unconnected-(U$2B-GPIO_7-PadP9.42)") (class "Default")
      (node (ref "U$2") (pin "P9.42") (pinfunction "GPIO_7_P9.42") (pintype "bidirectional"))
    )
    (net (code "95") (name "unconnected-(U$2B-GPIO_14-PadP9.26)") (class "Default")
      (node (ref "U$2") (pin "P9.26") (pinfunction "GPIO_14_P9.26") (pintype "bidirectional"))
    )
    (net (code "96") (name "unconnected-(U$2B-GPIO_15-PadP9.24)") (class "Default")
      (node (ref "U$2") (pin "P9.24") (pinfunction "GPIO_15_P9.24") (pintype "bidirectional"))
    )
    (net (code "97") (name "unconnected-(U$2B-GPIO_20-PadP9.41)") (class "Default")
      (node (ref "U$2") (pin "P9.41") (pinfunction "GPIO_20_P9.41") (pintype "bidirectional"))
    )
    (net (code "98") (name "unconnected-(U$2B-GPIO_30-PadP9.11)") (class "Default")
      (node (ref "U$2") (pin "P9.11") (pinfunction "GPIO_30_P9.11") (pintype "bidirectional"))
    )
    (net (code "99") (name "unconnected-(U$2B-GPIO_31-PadP9.13)") (class "Default")
      (node (ref "U$2") (pin "P9.13") (pinfunction "GPIO_31_P9.13") (pintype "bidirectional"))
    )
    (net (code "100") (name "unconnected-(U$2B-GPIO_40-PadP9.14)") (class "Default")
      (node (ref "U$2") (pin "P9.14") (pinfunction "GPIO_40_P9.14") (pintype "bidirectional"))
    )
    (net (code "101") (name "unconnected-(U$2B-GPIO_48-PadP9.15)") (class "Default")
      (node (ref "U$2") (pin "P9.15") (pinfunction "GPIO_48_P9.15") (pintype "bidirectional"))
    )
    (net (code "102") (name "unconnected-(U$2B-GPIO_49-PadP9.23)") (class "Default")
      (node (ref "U$2") (pin "P9.23") (pinfunction "GPIO_49_P9.23") (pintype "bidirectional"))
    )
    (net (code "103") (name "unconnected-(U$2B-GPIO_51-PadP9.16)") (class "Default")
      (node (ref "U$2") (pin "P9.16") (pinfunction "GPIO_51_P9.16") (pintype "bidirectional"))
    )
    (net (code "104") (name "unconnected-(U$2B-GPIO_60-PadP9.12)") (class "Default")
      (node (ref "U$2") (pin "P9.12") (pinfunction "GPIO_60_P9.12") (pintype "bidirectional"))
    )
    (net (code "105") (name "unconnected-(U$2B-GPIO_117-PadP9.25)") (class "Default")
      (node (ref "U$2") (pin "P9.25") (pinfunction "GPIO_117_P9.25") (pintype "bidirectional"))
    )
    (net (code "106") (name "unconnected-(U$2B-GPIO_120-PadP9.31)") (class "Default")
      (node (ref "U$2") (pin "P9.31") (pinfunction "GPIO_120_P9.31") (pintype "bidirectional"))
    )
    (net (code "107") (name "unconnected-(U$2B-GPIO_121-PadP9.29)") (class "Default")
      (node (ref "U$2") (pin "P9.29") (pinfunction "GPIO_121_P9.29") (pintype "bidirectional"))
    )
    (net (code "108") (name "unconnected-(U$2B-GPIO_122-PadP9.30)") (class "Default")
      (node (ref "U$2") (pin "P9.30") (pinfunction "GPIO_122_P9.30") (pintype "bidirectional"))
    )
    (net (code "109") (name "unconnected-(U$2B-GPIO_123-PadP9.28)") (class "Default")
      (node (ref "U$2") (pin "P9.28") (pinfunction "GPIO_123_P9.28") (pintype "bidirectional"))
    )
    (net (code "110") (name "unconnected-(U$2B-GPIO_125-PadP9.27)") (class "Default")
      (node (ref "U$2") (pin "P9.27") (pinfunction "GPIO_125_P9.27") (pintype "bidirectional"))
    )
    (net (code "111") (name "unconnected-(U$2B-PWR_BUT-PadP9.9)") (class "Default")
      (node (ref "U$2") (pin "P9.9") (pinfunction "PWR_BUT_P9.9") (pintype "bidirectional"))
    )
    (net (code "112") (name "unconnected-(U$2B-SYS_5V-PadP9.7)") (class "Default")
      (node (ref "U$2") (pin "P9.7") (pinfunction "SYS_5V_P9.7") (pintype "bidirectional"))
    )
    (net (code "113") (name "unconnected-(U$2B-SYS_5V-PadP9.8)") (class "Default")
      (node (ref "U$2") (pin "P9.8") (pinfunction "SYS_5V_P9.8") (pintype "bidirectional"))
    )
    (net (code "114") (name "unconnected-(U$2B-SYS_RESET~{N}-PadP9.10)") (class "Default")
      (node (ref "U$2") (pin "P9.10") (pinfunction "SYS_RESET~{N}_P9.10") (pintype "bidirectional"))
    )
    (net (code "115") (name "unconnected-(U$2B-VDD_3V3-PadP9.3)") (class "Default")
      (node (ref "U$2") (pin "P9.3") (pinfunction "VDD_3V3_P9.3") (pintype "bidirectional"))
    )
    (net (code "116") (name "unconnected-(U$2B-VDD_3V3-PadP9.4)") (class "Default")
      (node (ref "U$2") (pin "P9.4") (pinfunction "VDD_3V3_P9.4") (pintype "bidirectional"))
    )
    (net (code "117") (name "unconnected-(U$2B-VDD_5V-PadP9.5)") (class "Default")
      (node (ref "U$2") (pin "P9.5") (pinfunction "VDD_5V_P9.5") (pintype "bidirectional"))
    )
    (net (code "118") (name "unconnected-(U$2B-VDD_5V-PadP9.6)") (class "Default")
      (node (ref "U$2") (pin "P9.6") (pinfunction "VDD_5V_P9.6") (pintype "bidirectional"))
    )
    (net (code "119") (name "unconnected-(U$2B-VDD_ADC-PadP9.32)") (class "Default")
      (node (ref "U$2") (pin "P9.32") (pinfunction "VDD_ADC_P9.32") (pintype "bidirectional"))
    )
    (net (code "120") (name "unconnected-(U2-OUT-Pad2)") (class "Default")
      (node (ref "U2") (pin "2") (pinfunction "OUT_2") (pintype "output"))
    )
  )
)
